# RFM50_Breakout.net
KiCad netlist of a schematic drawn in EAGLE
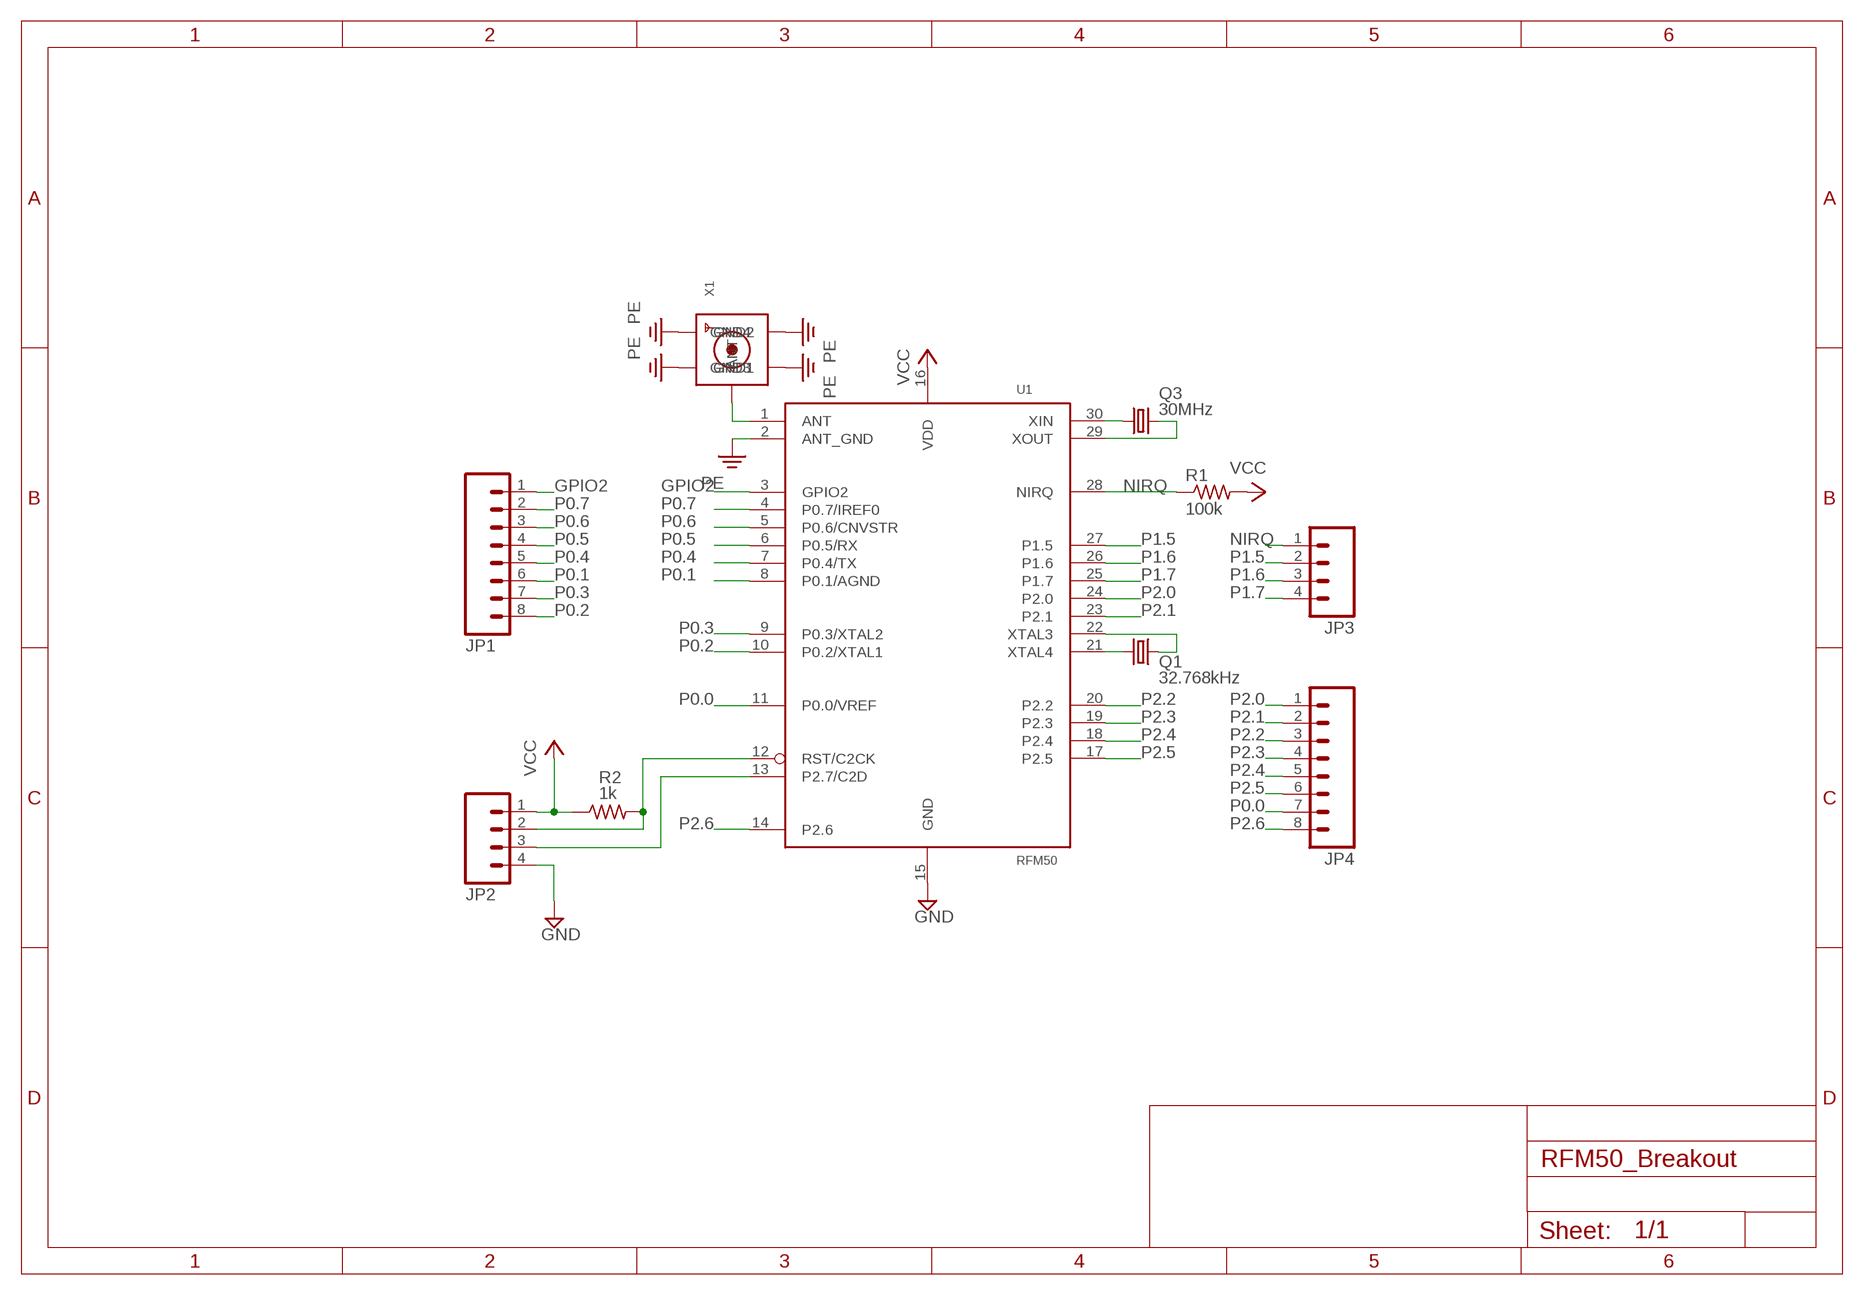
[diagram p0: schematic, sheet 1]

(export (version "E")
  (design (tool "Eeschema 10.0.6"))
  (components
    (comp (ref "JP1")
      (value "M081X08")
      (footprint "eagle-import:1X08")
      (libsource (lib "eagle-import") (part "M081X08"))
    )
    (comp (ref "JP2")
      (value "M04PTH")
      (footprint "eagle-import:1X04")
      (libsource (lib "eagle-import") (part "M04PTH"))
    )
    (comp (ref "JP3")
      (value "M04PTH")
      (footprint "eagle-import:1X04")
      (libsource (lib "eagle-import") (part "M04PTH"))
    )
    (comp (ref "JP4")
      (value "M081X08")
      (footprint "eagle-import:1X08")
      (libsource (lib "eagle-import") (part "M081X08"))
    )
    (comp (ref "Q1")
      (value "32.768kHz")
      (footprint "eagle-import:TC26H")
      (libsource (lib "eagle-import") (part "CRYSTALTC26H"))
    )
    (comp (ref "Q3")
      (value "30MHz")
      (footprint "eagle-import:HC49_S")
      (libsource (lib "eagle-import") (part "CRYSTALHC49S"))
    )
    (comp (ref "R1")
      (value "100k")
      (footprint "eagle-import:RCL_0204V")
      (libsource (lib "eagle-import") (part "RCL_R-US_0204/2V"))
    )
    (comp (ref "R2")
      (value "1k")
      (footprint "eagle-import:RCL_0204V")
      (libsource (lib "eagle-import") (part "RCL_R-US_0204/2V"))
    )
    (comp (ref "U1")
      (value "RFM50")
      (footprint "eagle-import:RFM50")
      (libsource (lib "eagle-import") (part "RFM50"))
    )
    (comp (ref "X1")
      (value "SMACONNECTOR")
      (footprint "eagle-import:SMA90_DIP")
      (libsource (lib "eagle-import") (part "SMACONNECTOR"))
    )
  )
  (nets
    (net (code "1") (name "/GPIO2") (class "Default")
      (node (ref "JP1") (pin "1") (pinfunction "1_1") (pintype "passive"))
      (node (ref "U1") (pin "3") (pinfunction "GPIO2_3") (pintype "bidirectional"))
    )
    (net (code "2") (name "/NIRQ") (class "Default")
      (node (ref "JP3") (pin "1") (pinfunction "1_1") (pintype "passive"))
      (node (ref "R1") (pin "1") (pinfunction "1_1") (pintype "passive"))
      (node (ref "U1") (pin "28") (pinfunction "NIRQ_28") (pintype "output"))
    )
    (net (code "3") (name "/P0.0") (class "Default")
      (node (ref "JP4") (pin "7") (pinfunction "7_7") (pintype "passive"))
      (node (ref "U1") (pin "11") (pinfunction "P0.0/VREF_11") (pintype "bidirectional"))
    )
    (net (code "4") (name "/P0.1") (class "Default")
      (node (ref "JP1") (pin "6") (pinfunction "6_6") (pintype "passive"))
      (node (ref "U1") (pin "8") (pinfunction "P0.1/AGND_8") (pintype "bidirectional"))
    )
    (net (code "5") (name "/P0.2") (class "Default")
      (node (ref "JP1") (pin "8") (pinfunction "8_8") (pintype "passive"))
      (node (ref "U1") (pin "10") (pinfunction "P0.2/XTAL1_10") (pintype "bidirectional"))
    )
    (net (code "6") (name "/P0.3") (class "Default")
      (node (ref "JP1") (pin "7") (pinfunction "7_7") (pintype "passive"))
      (node (ref "U1") (pin "9") (pinfunction "P0.3/XTAL2_9") (pintype "bidirectional"))
    )
    (net (code "7") (name "/P0.4") (class "Default")
      (node (ref "JP1") (pin "5") (pinfunction "5_5") (pintype "passive"))
      (node (ref "U1") (pin "7") (pinfunction "P0.4/TX_7") (pintype "bidirectional"))
    )
    (net (code "8") (name "/P0.5") (class "Default")
      (node (ref "JP1") (pin "4") (pinfunction "4_4") (pintype "passive"))
      (node (ref "U1") (pin "6") (pinfunction "P0.5/RX_6") (pintype "bidirectional"))
    )
    (net (code "9") (name "/P0.6") (class "Default")
      (node (ref "JP1") (pin "3") (pinfunction "3_3") (pintype "passive"))
      (node (ref "U1") (pin "5") (pinfunction "P0.6/CNVSTR_5") (pintype "bidirectional"))
    )
    (net (code "10") (name "/P0.7") (class "Default")
      (node (ref "JP1") (pin "2") (pinfunction "2_2") (pintype "passive"))
      (node (ref "U1") (pin "4") (pinfunction "P0.7/IREF0_4") (pintype "bidirectional"))
    )
    (net (code "11") (name "/P1.5") (class "Default")
      (node (ref "JP3") (pin "2") (pinfunction "2_2") (pintype "passive"))
      (node (ref "U1") (pin "27") (pinfunction "P1.5_27") (pintype "bidirectional"))
    )
    (net (code "12") (name "/P1.6") (class "Default")
      (node (ref "JP3") (pin "3") (pinfunction "3_3") (pintype "passive"))
      (node (ref "U1") (pin "26") (pinfunction "P1.6_26") (pintype "bidirectional"))
    )
    (net (code "13") (name "/P1.7") (class "Default")
      (node (ref "JP3") (pin "4") (pinfunction "4_4") (pintype "passive"))
      (node (ref "U1") (pin "25") (pinfunction "P1.7_25") (pintype "bidirectional"))
    )
    (net (code "14") (name "/P2.0") (class "Default")
      (node (ref "JP4") (pin "1") (pinfunction "1_1") (pintype "passive"))
      (node (ref "U1") (pin "24") (pinfunction "P2.0_24") (pintype "bidirectional"))
    )
    (net (code "15") (name "/P2.1") (class "Default")
      (node (ref "JP4") (pin "2") (pinfunction "2_2") (pintype "passive"))
      (node (ref "U1") (pin "23") (pinfunction "P2.1_23") (pintype "bidirectional"))
    )
    (net (code "16") (name "/P2.2") (class "Default")
      (node (ref "JP4") (pin "3") (pinfunction "3_3") (pintype "passive"))
      (node (ref "U1") (pin "20") (pinfunction "P2.2_20") (pintype "bidirectional"))
    )
    (net (code "17") (name "/P2.3") (class "Default")
      (node (ref "JP4") (pin "4") (pinfunction "4_4") (pintype "passive"))
      (node (ref "U1") (pin "19") (pinfunction "P2.3_19") (pintype "bidirectional"))
    )
    (net (code "18") (name "/P2.4") (class "Default")
      (node (ref "JP4") (pin "5") (pinfunction "5_5") (pintype "passive"))
      (node (ref "U1") (pin "18") (pinfunction "P2.4_18") (pintype "bidirectional"))
    )
    (net (code "19") (name "/P2.5") (class "Default")
      (node (ref "JP4") (pin "6") (pinfunction "6_6") (pintype "passive"))
      (node (ref "U1") (pin "17") (pinfunction "P2.5_17") (pintype "bidirectional"))
    )
    (net (code "20") (name "/P2.6") (class "Default")
      (node (ref "JP4") (pin "8") (pinfunction "8_8") (pintype "passive"))
      (node (ref "U1") (pin "14") (pinfunction "P2.6_14") (pintype "bidirectional"))
    )
    (net (code "21") (name "GND") (class "Default")
      (node (ref "JP2") (pin "4") (pinfunction "4_4") (pintype "passive"))
      (node (ref "U1") (pin "15") (pinfunction "GND_15") (pintype "bidirectional"))
    )
    (net (code "22") (name "Net-(U1-ANT)") (class "Default")
      (node (ref "U1") (pin "1") (pinfunction "ANT_1") (pintype "bidirectional"))
      (node (ref "X1") (pin "ANTENNA") (pinfunction "ANT_ANTENNA") (pintype "bidirectional"))
    )
    (net (code "23") (name "Net-(U1-P2.7{slash}C2D)") (class "Default")
      (node (ref "JP2") (pin "3") (pinfunction "3_3") (pintype "passive"))
      (node (ref "U1") (pin "13") (pinfunction "P2.7/C2D_13") (pintype "bidirectional"))
    )
    (net (code "24") (name "Net-(U1-RST{slash}C2CK)") (class "Default")
      (node (ref "JP2") (pin "2") (pinfunction "2_2") (pintype "passive"))
      (node (ref "R2") (pin "2") (pinfunction "2_2") (pintype "passive"))
      (node (ref "U1") (pin "12") (pinfunction "RST/C2CK_12") (pintype "bidirectional"))
    )
    (net (code "25") (name "Net-(U1-XIN)") (class "Default")
      (node (ref "Q3") (pin "1") (pinfunction "1_1") (pintype "passive"))
      (node (ref "U1") (pin "30") (pinfunction "XIN_30") (pintype "input"))
    )
    (net (code "26") (name "Net-(U1-XOUT)") (class "Default")
      (node (ref "Q3") (pin "2") (pinfunction "2_2") (pintype "passive"))
      (node (ref "U1") (pin "29") (pinfunction "XOUT_29") (pintype "output"))
    )
    (net (code "27") (name "Net-(U1-XTAL3)") (class "Default")
      (node (ref "Q1") (pin "1") (pinfunction "1_1") (pintype "passive"))
      (node (ref "U1") (pin "22") (pinfunction "XTAL3_22") (pintype "bidirectional"))
    )
    (net (code "28") (name "Net-(U1-XTAL4)") (class "Default")
      (node (ref "Q1") (pin "2") (pinfunction "2_2") (pintype "passive"))
      (node (ref "U1") (pin "21") (pinfunction "XTAL4_21") (pintype "bidirectional"))
    )
    (net (code "29") (name "PE") (class "Default")
      (node (ref "U1") (pin "2") (pinfunction "ANT_GND_2") (pintype "bidirectional"))
      (node (ref "X1") (pin "GND1") (pinfunction "GND1_GND1") (pintype "power_in"))
      (node (ref "X1") (pin "GND2") (pinfunction "GND2_GND2") (pintype "power_in"))
      (node (ref "X1") (pin "GND3") (pinfunction "GND3_GND3") (pintype "power_in"))
      (node (ref "X1") (pin "GND4") (pinfunction "GND4_GND4") (pintype "power_in"))
    )
    (net (code "30") (name "VCC") (class "Default")
      (node (ref "JP2") (pin "1") (pinfunction "1_1") (pintype "passive"))
      (node (ref "R1") (pin "2") (pinfunction "2_2") (pintype "passive"))
      (node (ref "R2") (pin "1") (pinfunction "1_1") (pintype "passive"))
      (node (ref "U1") (pin "16") (pinfunction "VDD_16") (pintype "power_in"))
    )
  )
)
